# 8296_Diag_J4.net
KiCad netlist of a schematic drawn in EAGLE
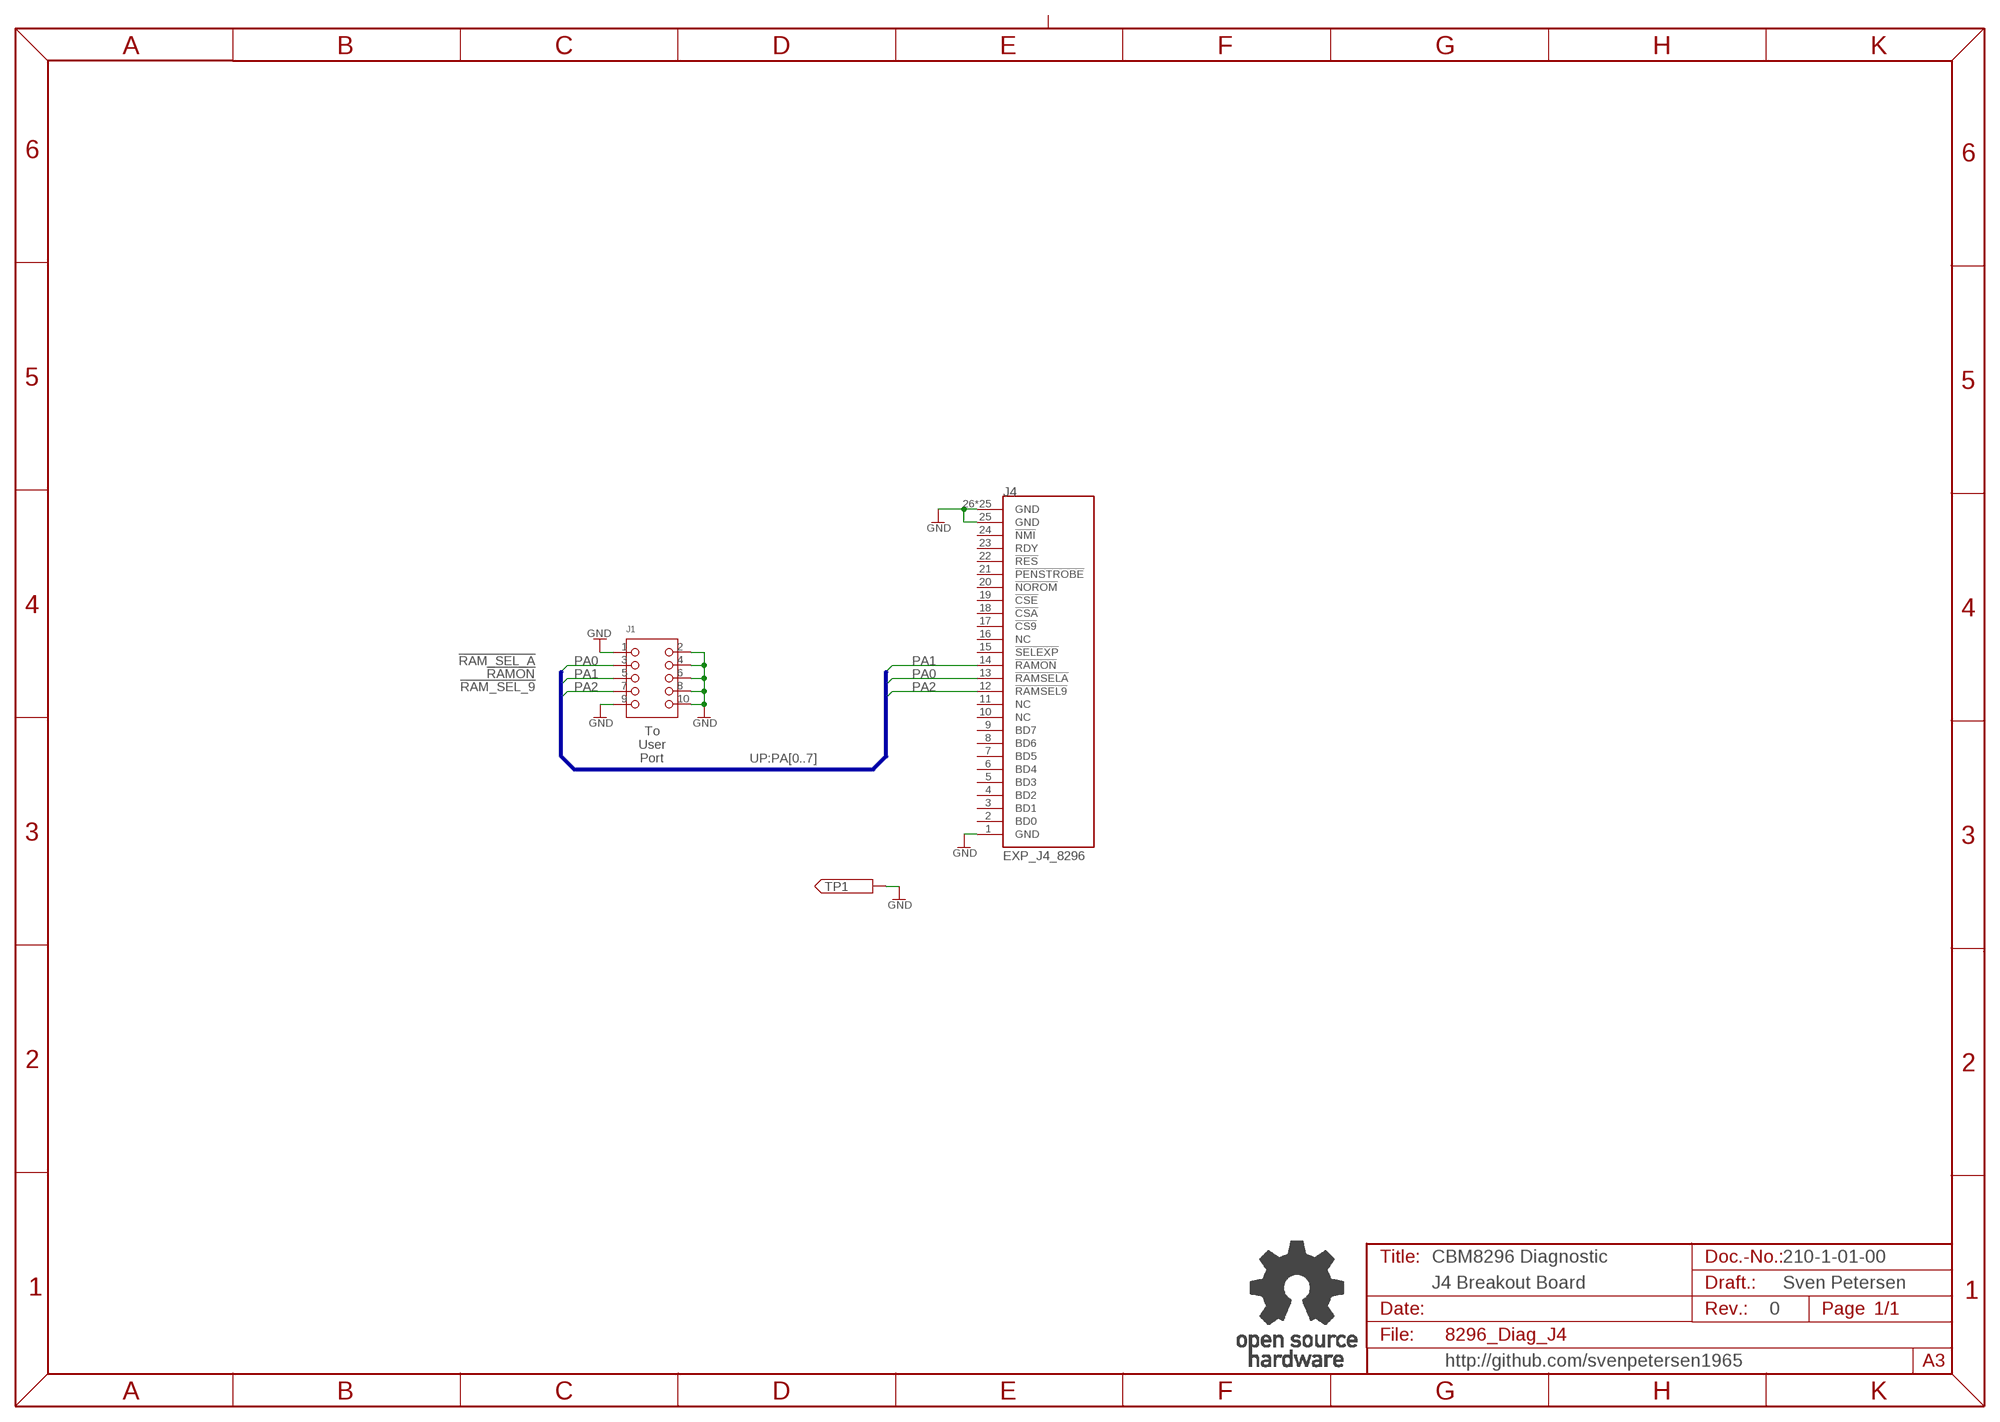
[diagram p0: schematic, sheet 1]

(export (version "E")
  (design (tool "Eeschema 10.0.6"))
  (components
    (comp (ref "J1")
      (value "2X05WV")
      (footprint "eagle-import:2X05WV")
      (libsource (lib "eagle-import") (part "2X05WV"))
    )
    (comp (ref "J4")
      (value "EXP_J4_8296")
      (footprint "eagle-import:PET_EXPANSION_BOT")
      (libsource (lib "eagle-import") (part "EXP_J4_8296"))
    )
    (comp (ref "TP1")
      (value "PINHD-1X1")
      (footprint "eagle-import:1X01")
      (libsource (lib "eagle-import") (part "PINHD-1X1"))
    )
    (comp (ref "U$5")
      (value "OPEN_SOURCE_HW")
      (footprint "eagle-import:OPENHW")
      (libsource (lib "eagle-import") (part "OPEN_SOURCE_HW"))
    )
  )
  (nets
    (net (code "9") (name "/PA0") (class "Default")
      (node (ref "J1") (pin "3") (pinfunction "3_3") (pintype "passive"))
      (node (ref "J4") (pin "13") (pinfunction "~{RAMSELA}_13") (pintype "input"))
    )
    (net (code "10") (name "/PA1") (class "Default")
      (node (ref "J1") (pin "5") (pinfunction "5_5") (pintype "passive"))
      (node (ref "J4") (pin "14") (pinfunction "~{RAMON}_14") (pintype "input"))
    )
    (net (code "11") (name "/PA2") (class "Default")
      (node (ref "J1") (pin "7") (pinfunction "7_7") (pintype "passive"))
      (node (ref "J4") (pin "12") (pinfunction "~{RAMSEL9}_12") (pintype "input"))
    )
    (net (code "13") (name "GND") (class "Default")
      (node (ref "J1") (pin "1") (pinfunction "1_1") (pintype "passive"))
      (node (ref "J1") (pin "10") (pinfunction "10_10") (pintype "passive"))
      (node (ref "J1") (pin "2") (pinfunction "2_2") (pintype "passive"))
      (node (ref "J1") (pin "4") (pinfunction "4_4") (pintype "passive"))
      (node (ref "J1") (pin "6") (pinfunction "6_6") (pintype "passive"))
      (node (ref "J1") (pin "8") (pinfunction "8_8") (pintype "passive"))
      (node (ref "J1") (pin "9") (pinfunction "9_9") (pintype "passive"))
      (node (ref "J4") (pin "1") (pinfunction "GND_1") (pintype "power_in"))
      (node (ref "J4") (pin "25") (pinfunction "GND_25") (pintype "power_in"))
      (node (ref "J4") (pin "26") (pinfunction "GND_26") (pintype "power_in"))
      (node (ref "J4") (pin "27") (pinfunction "GND_27") (pintype "power_in"))
      (node (ref "J4") (pin "28") (pinfunction "GND_28") (pintype "power_in"))
      (node (ref "J4") (pin "29") (pinfunction "GND_29") (pintype "power_in"))
      (node (ref "J4") (pin "30") (pinfunction "GND_30") (pintype "power_in"))
      (node (ref "J4") (pin "31") (pinfunction "GND_31") (pintype "power_in"))
      (node (ref "J4") (pin "32") (pinfunction "GND_32") (pintype "power_in"))
      (node (ref "J4") (pin "33") (pinfunction "GND_33") (pintype "power_in"))
      (node (ref "J4") (pin "34") (pinfunction "GND_34") (pintype "power_in"))
      (node (ref "J4") (pin "35") (pinfunction "GND_35") (pintype "power_in"))
      (node (ref "J4") (pin "36") (pinfunction "GND_36") (pintype "power_in"))
      (node (ref "J4") (pin "37") (pinfunction "GND_37") (pintype "power_in"))
      (node (ref "J4") (pin "38") (pinfunction "GND_38") (pintype "power_in"))
      (node (ref "J4") (pin "39") (pinfunction "GND_39") (pintype "power_in"))
      (node (ref "J4") (pin "40") (pinfunction "GND_40") (pintype "power_in"))
      (node (ref "J4") (pin "41") (pinfunction "GND_41") (pintype "power_in"))
      (node (ref "J4") (pin "42") (pinfunction "GND_42") (pintype "power_in"))
      (node (ref "J4") (pin "43") (pinfunction "GND_43") (pintype "power_in"))
      (node (ref "J4") (pin "44") (pinfunction "GND_44") (pintype "power_in"))
      (node (ref "J4") (pin "45") (pinfunction "GND_45") (pintype "power_in"))
      (node (ref "J4") (pin "46") (pinfunction "GND_46") (pintype "power_in"))
      (node (ref "J4") (pin "47") (pinfunction "GND_47") (pintype "power_in"))
      (node (ref "J4") (pin "48") (pinfunction "GND_48") (pintype "power_in"))
      (node (ref "J4") (pin "49") (pinfunction "GND_49") (pintype "power_in"))
      (node (ref "J4") (pin "50") (pinfunction "GND_50") (pintype "power_in"))
      (node (ref "TP1") (pin "1") (pinfunction "1_1") (pintype "passive"))
    )
    (net (code "14") (name "unconnected-(J4-BD0-Pad2)") (class "Default")
      (node (ref "J4") (pin "2") (pinfunction "BD0_2") (pintype "bidirectional"))
    )
    (net (code "15") (name "unconnected-(J4-BD1-Pad3)") (class "Default")
      (node (ref "J4") (pin "3") (pinfunction "BD1_3") (pintype "bidirectional"))
    )
    (net (code "16") (name "unconnected-(J4-BD2-Pad4)") (class "Default")
      (node (ref "J4") (pin "4") (pinfunction "BD2_4") (pintype "bidirectional"))
    )
    (net (code "17") (name "unconnected-(J4-BD3-Pad5)") (class "Default")
      (node (ref "J4") (pin "5") (pinfunction "BD3_5") (pintype "bidirectional"))
    )
    (net (code "18") (name "unconnected-(J4-BD4-Pad6)") (class "Default")
      (node (ref "J4") (pin "6") (pinfunction "BD4_6") (pintype "bidirectional"))
    )
    (net (code "19") (name "unconnected-(J4-BD5-Pad7)") (class "Default")
      (node (ref "J4") (pin "7") (pinfunction "BD5_7") (pintype "bidirectional"))
    )
    (net (code "20") (name "unconnected-(J4-BD6-Pad8)") (class "Default")
      (node (ref "J4") (pin "8") (pinfunction "BD6_8") (pintype "bidirectional"))
    )
    (net (code "21") (name "unconnected-(J4-BD7-Pad9)") (class "Default")
      (node (ref "J4") (pin "9") (pinfunction "BD7_9") (pintype "bidirectional"))
    )
    (net (code "22") (name "unconnected-(J4-NC-Pad10)") (class "Default")
      (node (ref "J4") (pin "10") (pinfunction "NC_10") (pintype "passive"))
    )
    (net (code "23") (name "unconnected-(J4-NC-Pad11)") (class "Default")
      (node (ref "J4") (pin "11") (pinfunction "NC_11") (pintype "passive"))
    )
    (net (code "24") (name "unconnected-(J4-NC-Pad16)") (class "Default")
      (node (ref "J4") (pin "16") (pinfunction "NC_16") (pintype "input"))
    )
    (net (code "25") (name "unconnected-(J4-RDY-Pad23)") (class "Default")
      (node (ref "J4") (pin "23") (pinfunction "RDY_23") (pintype "output"))
    )
    (net (code "26") (name "unconnected-(J4-~{CS9}-Pad17)") (class "Default")
      (node (ref "J4") (pin "17") (pinfunction "~{CS9}_17") (pintype "input"))
    )
    (net (code "27") (name "unconnected-(J4-~{CSA}-Pad18)") (class "Default")
      (node (ref "J4") (pin "18") (pinfunction "~{CSA}_18") (pintype "input"))
    )
    (net (code "28") (name "unconnected-(J4-~{CSE}-Pad19)") (class "Default")
      (node (ref "J4") (pin "19") (pinfunction "~{CSE}_19") (pintype "input"))
    )
    (net (code "29") (name "unconnected-(J4-~{NMI}-Pad24)") (class "Default")
      (node (ref "J4") (pin "24") (pinfunction "~{NMI}_24") (pintype "bidirectional"))
    )
    (net (code "30") (name "unconnected-(J4-~{NOROM}-Pad20)") (class "Default")
      (node (ref "J4") (pin "20") (pinfunction "~{NOROM}_20") (pintype "bidirectional"))
    )
    (net (code "31") (name "unconnected-(J4-~{PENSTROBE}-Pad21)") (class "Default")
      (node (ref "J4") (pin "21") (pinfunction "~{PENSTROBE}_21") (pintype "output"))
    )
    (net (code "32") (name "unconnected-(J4-~{RES}-Pad22)") (class "Default")
      (node (ref "J4") (pin "22") (pinfunction "~{RES}_22") (pintype "bidirectional"))
    )
    (net (code "33") (name "unconnected-(J4-~{SELEXP}-Pad15)") (class "Default")
      (node (ref "J4") (pin "15") (pinfunction "~{SELEXP}_15") (pintype "input"))
    )
  )
)
